# bidirectional_switch.net
KiCad netlist of a schematic drawn in Altium Designer
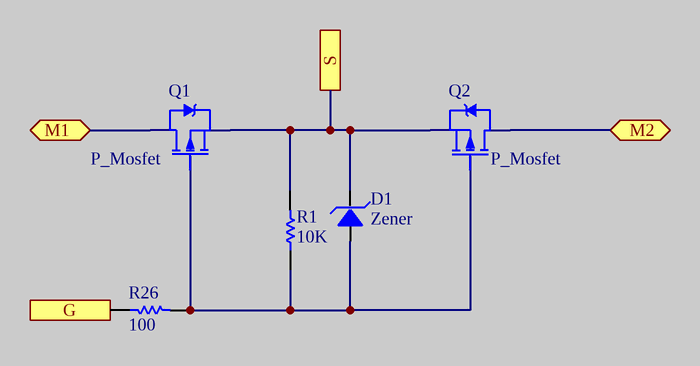
[diagram p0: bidirectional_switch.SchDoc]

(export (version "E")
  (design (tool "Eeschema 10.0.6"))
  (components
    (comp (ref "D1") (value "Zener") (footprint "ZENER") (libsource (lib "eLIB") (part "Zener")))
    (comp (ref "Q1") (value "P_Mosfet") (footprint "dpak") (libsource (lib "eLIB") (part "P_Mosfet IRF5305")))
    (comp (ref "Q2") (value "P_Mosfet") (footprint "dpak") (libsource (lib "eLIB") (part "P_Mosfet IRF5305")))
    (comp (ref "R1")
      (value "10K")
      (footprint "RESC0603")
      (description "0603,0.1W")
      (fields (field (name "PUBLISHER") "Altium Limited"))
      (libsource (lib "eLIB") (part "Resistor"))
    )
    (comp (ref "R26")
      (value "100")
      (footprint "RESC0603")
      (description "0603,0.1W")
      (fields (field (name "PUBLISHER") "Altium Limited"))
      (libsource (lib "eLIB") (part "Resistor"))
    )
  )
  (nets
    (net (code "1") (name "/G") (class "Default")
      (node (ref "R26") (pin "1") (pinfunction "1_1") (pintype "passive"))
    )
    (net (code "2") (name "/M1") (class "Default")
      (node (ref "Q1") (pin "2") (pinfunction "D_2") (pintype "passive"))
    )
    (net (code "3") (name "/M2") (class "Default")
      (node (ref "Q2") (pin "2") (pinfunction "D_2") (pintype "passive"))
    )
    (net (code "4") (name "/S") (class "Default")
      (node (ref "D1") (pin "2") (pinfunction "K_2") (pintype "passive"))
      (node (ref "Q1") (pin "3") (pinfunction "S_3") (pintype "passive"))
      (node (ref "Q2") (pin "3") (pinfunction "S_3") (pintype "passive"))
      (node (ref "R1") (pin "2") (pinfunction "2_2") (pintype "passive"))
    )
    (net (code "5") (name "Net-(D1-A)") (class "Default")
      (node (ref "D1") (pin "1") (pinfunction "A_1") (pintype "passive"))
      (node (ref "Q1") (pin "1") (pinfunction "G_1") (pintype "passive"))
      (node (ref "Q2") (pin "1") (pinfunction "G_1") (pintype "passive"))
      (node (ref "R1") (pin "1") (pinfunction "1_1") (pintype "passive"))
      (node (ref "R26") (pin "2") (pinfunction "2_2") (pintype "passive"))
    )
  )
)
